# ethernet.net
KiCad netlist of a schematic drawn in Altium Designer
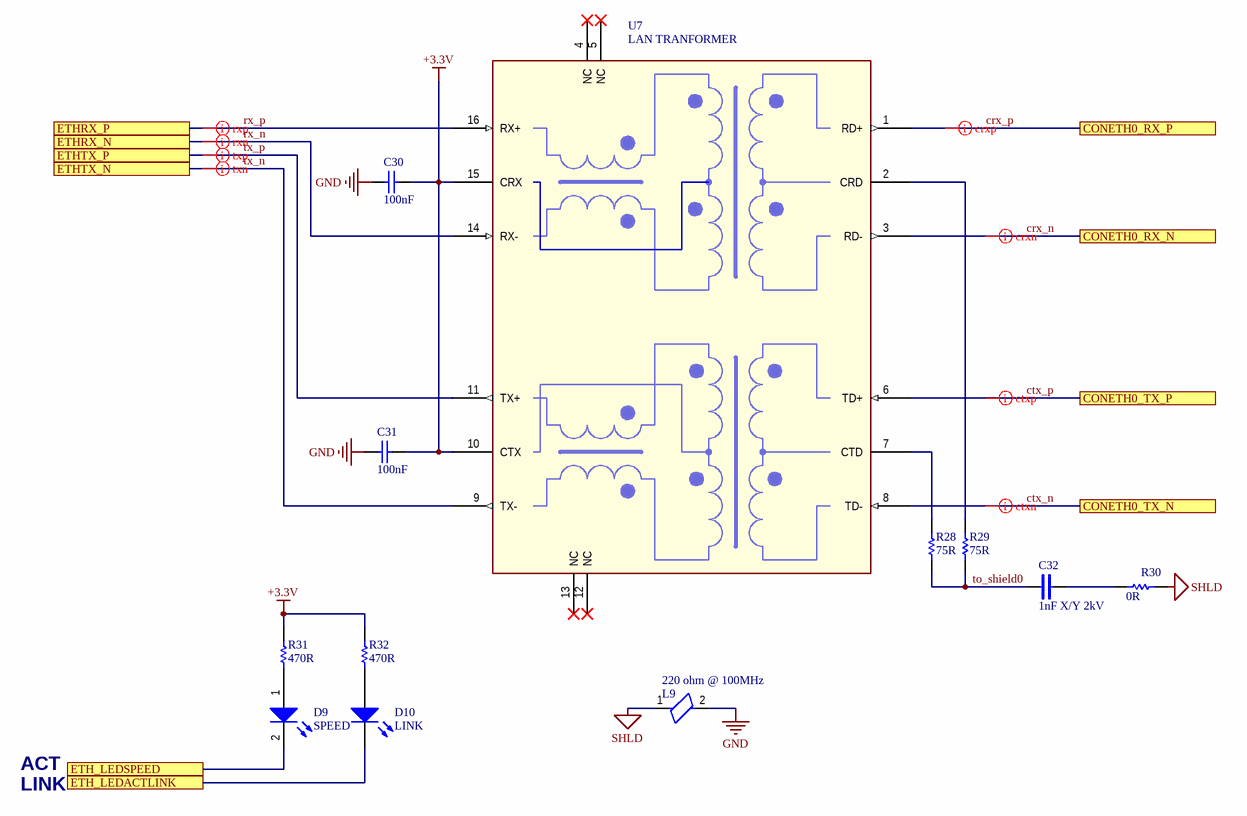
[diagram p0: ethernet.SchDoc]

(export (version "E")
  (design (tool "Eeschema 10.0.6"))
  (components
    (comp (ref "C30")
      (value "100nF")
      (footprint "0603_[1608]")
      (description "Ceramic X7R 50V")
      (fields (field (name "PUBLISHER") "Altium Limited"))
      (libsource (lib "DEVELER_Library") (part "Cap"))
    )
    (comp (ref "C31")
      (value "100nF")
      (footprint "0603_[1608]")
      (description "Ceramic X7R 50V")
      (fields (field (name "PUBLISHER") "Altium Limited"))
      (libsource (lib "DEVELER_Library") (part "Cap"))
    )
    (comp (ref "C32")
      (value "1nF X/Y 2kV")
      (footprint "1808_[4520]")
      (description "CER 250VAC X7R X1/Y1 (GA342DR7GF102KW)")
      (libsource (lib "DEVELER_Library") (part "cap_xy"))
    )
    (comp (ref "D9")
      (value "SPEED")
      (footprint "0603_[1608]_K2-A1_LED")
      (description "LED Green")
      (fields (field (name "PUBLISHER") "Altium Limited"))
      (libsource (lib "DEVELER_Library") (part "LED0"))
    )
    (comp (ref "D10")
      (value "LINK")
      (footprint "0603_[1608]_K2-A1_LED")
      (description "LED Green")
      (fields (field (name "PUBLISHER") "Altium Limited"))
      (libsource (lib "") (part "LED0_1"))
    )
    (comp (ref "L9")
      (value "220 ohm @ 100MHz")
      (footprint "0805_[2012]")
      (description "WE 742792022")
      (libsource (lib "project42_lib") (part "Ferrite Bead"))
    )
    (comp (ref "R28")
      (value "75R")
      (footprint "0603_[1608]")
      (description "Resistor")
      (libsource (lib "") (part "Res1_2"))
    )
    (comp (ref "R29")
      (value "75R")
      (footprint "0603_[1608]")
      (description "Resistor")
      (libsource (lib "") (part "Res1_2"))
    )
    (comp (ref "R30")
      (value "0R")
      (footprint "0603_[1608]")
      (description "Resistor")
      (fields (field (name "PUBLISHER") "Altium Limited"))
      (libsource (lib "") (part "Res1_1"))
    )
    (comp (ref "R31")
      (value "470R")
      (footprint "0603_[1608]")
      (description "Resistor")
      (fields (field (name "PUBLISHER") "Altium Limited"))
      (libsource (lib "DEVELER_Library") (part "Res1"))
    )
    (comp (ref "R32")
      (value "470R")
      (footprint "0603_[1608]")
      (description "Resistor")
      (fields (field (name "PUBLISHER") "Altium Limited"))
      (libsource (lib "DEVELER_Library") (part "Res1"))
    )
    (comp (ref "U7")
      (value "LAN TRANFORMER")
      (footprint "LAN_TR_1.27MM_SMD")
      (description "Lan transformer (WE 7490100111A (side A); WE 7490100161A (side B))")
      (libsource (lib "DEVELER_Library") (part "LAN-TR-WE7490100111A"))
    )
  )
  (nets
    (net (code "1") (name "+3.3V") (class "Default")
      (node (ref "C30") (pin "2") (pinfunction "2_2") (pintype "passive"))
      (node (ref "C31") (pin "2") (pinfunction "2_2") (pintype "passive"))
      (node (ref "R31") (pin "2") (pinfunction "2_2") (pintype "passive"))
      (node (ref "R32") (pin "2") (pinfunction "2_2") (pintype "passive"))
      (node (ref "U7") (pin "10") (pinfunction "CTX_10") (pintype "passive"))
      (node (ref "U7") (pin "15") (pinfunction "CRX_15") (pintype "passive"))
    )
    (net (code "2") (name "/ETH_LEDACTLINK") (class "Default")
      (node (ref "D10") (pin "2") (pinfunction "K_2") (pintype "passive"))
    )
    (net (code "3") (name "/ETH_LEDSPEED") (class "Default")
      (node (ref "D9") (pin "2") (pinfunction "K_2") (pintype "passive"))
    )
    (net (code "4") (name "/crx_n") (class "Default")
      (node (ref "U7") (pin "3") (pinfunction "RD-_3") (pintype "output"))
    )
    (net (code "5") (name "/crx_p") (class "Default")
      (node (ref "U7") (pin "1") (pinfunction "RD+_1") (pintype "output"))
    )
    (net (code "6") (name "/ctx_n") (class "Default")
      (node (ref "U7") (pin "8") (pinfunction "TD-_8") (pintype "input"))
    )
    (net (code "7") (name "/ctx_p") (class "Default")
      (node (ref "U7") (pin "6") (pinfunction "TD+_6") (pintype "input"))
    )
    (net (code "8") (name "/rx_n") (class "Default")
      (node (ref "U7") (pin "14") (pinfunction "RX-_14") (pintype "input"))
    )
    (net (code "9") (name "/rx_p") (class "Default")
      (node (ref "U7") (pin "16") (pinfunction "RX+_16") (pintype "input"))
    )
    (net (code "10") (name "/to_shield0") (class "Default")
      (node (ref "C32") (pin "1") (pinfunction "1_1") (pintype "passive"))
      (node (ref "R28") (pin "1") (pinfunction "1_1") (pintype "passive"))
      (node (ref "R29") (pin "1") (pinfunction "1_1") (pintype "passive"))
    )
    (net (code "11") (name "/tx_n") (class "Default")
      (node (ref "U7") (pin "9") (pinfunction "TX-_9") (pintype "output"))
    )
    (net (code "12") (name "/tx_p") (class "Default")
      (node (ref "U7") (pin "11") (pinfunction "TX+_11") (pintype "output"))
    )
    (net (code "13") (name "GND") (class "Default")
      (node (ref "C30") (pin "1") (pinfunction "1_1") (pintype "passive"))
      (node (ref "C31") (pin "1") (pinfunction "1_1") (pintype "passive"))
      (node (ref "L9") (pin "2") (pinfunction "2_2") (pintype "passive"))
    )
    (net (code "14") (name "Net-(C32-Pad2)") (class "Default")
      (node (ref "C32") (pin "2") (pinfunction "2_2") (pintype "passive"))
      (node (ref "R30") (pin "2") (pinfunction "2_2") (pintype "passive"))
    )
    (net (code "15") (name "Net-(D9-A)") (class "Default")
      (node (ref "D9") (pin "1") (pinfunction "A_1") (pintype "passive"))
      (node (ref "R31") (pin "1") (pinfunction "1_1") (pintype "passive"))
    )
    (net (code "16") (name "Net-(D10-A)") (class "Default")
      (node (ref "D10") (pin "1") (pinfunction "A_1") (pintype "passive"))
      (node (ref "R32") (pin "1") (pinfunction "1_1") (pintype "passive"))
    )
    (net (code "17") (name "Net-(U7-CRD)") (class "Default")
      (node (ref "R29") (pin "2") (pinfunction "2_2") (pintype "passive"))
      (node (ref "U7") (pin "2") (pinfunction "CRD_2") (pintype "passive"))
    )
    (net (code "18") (name "Net-(U7-CTD)") (class "Default")
      (node (ref "R28") (pin "2") (pinfunction "2_2") (pintype "passive"))
      (node (ref "U7") (pin "7") (pinfunction "CTD_7") (pintype "passive"))
    )
    (net (code "19") (name "SHLD") (class "Default")
      (node (ref "L9") (pin "1") (pinfunction "1_1") (pintype "passive"))
      (node (ref "R30") (pin "1") (pinfunction "1_1") (pintype "passive"))
    )
    (net (code "20") (name "unconnected-(U7-NC-Pad4)") (class "Default")
      (node (ref "U7") (pin "4") (pinfunction "NC_4") (pintype "passive+no_connect"))
    )
    (net (code "21") (name "unconnected-(U7-NC-Pad5)") (class "Default")
      (node (ref "U7") (pin "5") (pinfunction "NC_5") (pintype "passive+no_connect"))
    )
    (net (code "22") (name "unconnected-(U7-NC-Pad12)") (class "Default")
      (node (ref "U7") (pin "12") (pinfunction "NC_12") (pintype "passive+no_connect"))
    )
    (net (code "23") (name "unconnected-(U7-NC-Pad13)") (class "Default")
      (node (ref "U7") (pin "13") (pinfunction "NC_13") (pintype "passive+no_connect"))
    )
  )
)
